# Safety_Loop.net
KiCad netlist of a schematic drawn in Altium Designer
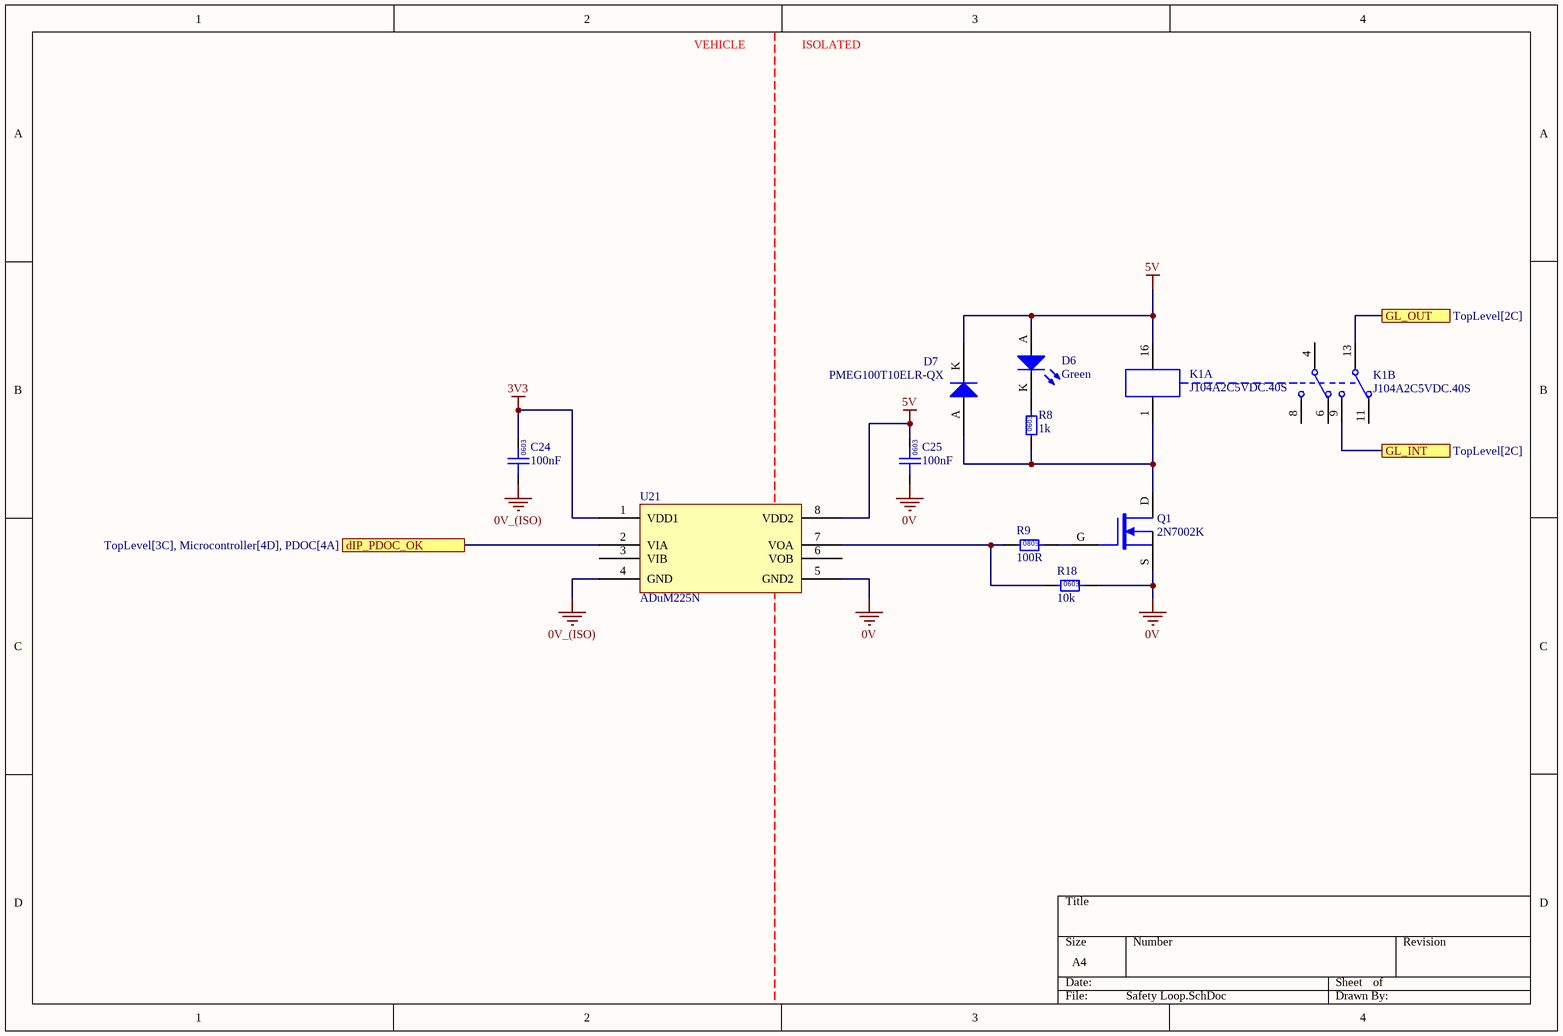
[diagram p0: Safety Loop.SchDoc]

(export (version "E")
  (design (tool "Eeschema 10.0.6"))
  (components
    (comp (ref "C24")
      (value "100nF")
      (footprint "0603")
      (fields
        (field (name "PART NUMBER") "GCM188L81H104KA57D")
        (field (name "MANUFACTURER") "muRata")
        (field (name "TOLERANCE") "±10%")
      )
      (libsource (lib "ts_standard_library") (part "Capacitor 0603"))
    )
    (comp (ref "C25")
      (value "100nF")
      (footprint "0603")
      (fields
        (field (name "PART NUMBER") "GCM188L81H104KA57D")
        (field (name "MANUFACTURER") "muRata")
        (field (name "TOLERANCE") "±10%")
      )
      (libsource (lib "ts_standard_library") (part "Capacitor 0603"))
    )
    (comp (ref "D6")
      (value "Green")
      (footprint "0805 LED")
      (description "Green LED Indication - Discrete 1.75V 0805 (2012 Metric)")
      (fields (field (name "PART NUMBER") "SML-210FTT86") (field (name "MANUFACTURER") "ROHM Semiconductor"))
      (libsource (lib "ts_standard_library") (part "LED"))
    )
    (comp (ref "D7")
      (value "PMEG100T10ELR-QX")
      (footprint "SODFL350X110-2N")
      (description "Diode 100 V 1A Surface Mount SOD-123W")
      (libsource (lib "Team Swinburne") (part "PMEG100T10ELR-QX"))
    )
    (comp (ref "K1")
      (value "J104A2C5VDC.40S")
      (footprint "J104A2C5VDC.40S-Footprint-1")
      (description "Relay Gen Purpose DPDT 3A 5V")
      (libsource (lib "") (part "J104A2C5VDC.40S_1"))
    )
    (comp (ref "Q1")
      (value "2N7002K")
      (footprint "2N7002K-Footprint-1")
      (description "60V 380mA, NFET MOSTFET (Small Signal)")
      (libsource (lib "Team Swinburne") (part "2N7002K"))
    )
    (comp (ref "R8")
      (value "1k")
      (footprint "0603")
      (fields
        (field (name "PART NUMBER") "RC0603FR-071KL")
        (field (name "MANUFACTURER") "YAGEO")
        (field (name "TOLERANCE") "0.01")
      )
      (libsource (lib "ts_standard_library") (part "Resistor 0603"))
    )
    (comp (ref "R9")
      (value "100R")
      (footprint "0805")
      (fields
        (field (name "PART NUMBER") "RC0805FR07100RL")
        (field (name "MANUFACTURER") "YAGEO")
        (field (name "TOLERANCE") "0.01")
      )
      (libsource (lib "ts_standard_library") (part "Resistor 0805"))
    )
    (comp (ref "R18")
      (value "10k")
      (footprint "0603")
      (fields
        (field (name "PART NUMBER") "RC0603FR-0710KL")
        (field (name "MANUFACTURER") "YAGEO")
        (field (name "TOLERANCE") "0.01")
      )
      (libsource (lib "ts_standard_library") (part "Resistor 0603"))
    )
    (comp (ref "U21")
      (value "ADuM225N")
      (footprint "AD-SOIC-8W")
      (description "DIGITAL ISOLATOR, DUAL CHANNEL")
      (fields (field (name "MANUFACTURER") "Analogue Devices"))
      (libsource (lib "ts_standard_library") (part "ADuM225N"))
    )
  )
  (nets
    (net (code "1") (name "/GL_INT") (class "Default")
      (node (ref "K1") (pin "9") (pinfunction "9_9") (pintype "passive"))
    )
    (net (code "2") (name "/GL_OUT") (class "Default")
      (node (ref "K1") (pin "13") (pinfunction "13_13") (pintype "passive"))
    )
    (net (code "3") (name "/dIP_PDOC_OK") (class "Default")
      (node (ref "U21") (pin "2") (pinfunction "VIA_2") (pintype "passive"))
    )
    (net (code "4") (name "0V") (class "Default")
      (node (ref "C25") (pin "1") (pinfunction "1_1") (pintype "passive"))
      (node (ref "Q1") (pin "S") (pinfunction "S_S") (pintype "passive"))
      (node (ref "R18") (pin "2") (pinfunction "2_2") (pintype "passive"))
      (node (ref "U21") (pin "5") (pinfunction "GND2_5") (pintype "passive"))
    )
    (net (code "5") (name "0V_(ISO)") (class "Default")
      (node (ref "C24") (pin "1") (pinfunction "1_1") (pintype "passive"))
      (node (ref "U21") (pin "4") (pinfunction "GND_4") (pintype "passive"))
    )
    (net (code "6") (name "3V3") (class "Default")
      (node (ref "C24") (pin "2") (pinfunction "2_2") (pintype "passive"))
      (node (ref "U21") (pin "1") (pinfunction "VDD1_1") (pintype "passive"))
    )
    (net (code "7") (name "5V") (class "Default")
      (node (ref "C25") (pin "2") (pinfunction "2_2") (pintype "passive"))
      (node (ref "D6") (pin "A") (pinfunction "A_A") (pintype "passive"))
      (node (ref "D7") (pin "K") (pintype "passive"))
      (node (ref "K1") (pin "16") (pinfunction "16_16") (pintype "passive"))
      (node (ref "U21") (pin "8") (pinfunction "VDD2_8") (pintype "passive"))
    )
    (net (code "8") (name "Net-(D6-PadK)") (class "Default")
      (node (ref "D6") (pin "K") (pinfunction "K_K") (pintype "passive"))
      (node (ref "R8") (pin "2") (pinfunction "2_2") (pintype "passive"))
    )
    (net (code "9") (name "Net-(D7-PadA)") (class "Default")
      (node (ref "D7") (pin "A") (pintype "passive"))
      (node (ref "K1") (pin "1") (pinfunction "1_1") (pintype "passive"))
      (node (ref "Q1") (pin "D") (pinfunction "D_D") (pintype "passive"))
      (node (ref "R8") (pin "1") (pinfunction "1_1") (pintype "passive"))
    )
    (net (code "10") (name "Net-(Q1-PadG)") (class "Default")
      (node (ref "Q1") (pin "G") (pinfunction "G_G") (pintype "passive"))
      (node (ref "R9") (pin "2") (pinfunction "2_2") (pintype "passive"))
    )
    (net (code "11") (name "Net-(U21-VOA)") (class "Default")
      (node (ref "R18") (pin "1") (pinfunction "1_1") (pintype "passive"))
      (node (ref "R9") (pin "1") (pinfunction "1_1") (pintype "passive"))
      (node (ref "U21") (pin "7") (pinfunction "VOA_7") (pintype "passive"))
    )
    (net (code "12") (name "unconnected-(K1-Pad4)") (class "Default")
      (node (ref "K1") (pin "4") (pinfunction "4_4") (pintype "passive"))
    )
    (net (code "13") (name "unconnected-(K1-Pad6)") (class "Default")
      (node (ref "K1") (pin "6") (pinfunction "6_6") (pintype "passive"))
    )
    (net (code "14") (name "unconnected-(K1-Pad8)") (class "Default")
      (node (ref "K1") (pin "8") (pinfunction "8_8") (pintype "passive"))
    )
    (net (code "15") (name "unconnected-(K1-Pad11)") (class "Default")
      (node (ref "K1") (pin "11") (pinfunction "11_11") (pintype "passive"))
    )
    (net (code "16") (name "unconnected-(U21-VIB-Pad3)") (class "Default")
      (node (ref "U21") (pin "3") (pinfunction "VIB_3") (pintype "passive"))
    )
    (net (code "17") (name "unconnected-(U21-VOB-Pad6)") (class "Default")
      (node (ref "U21") (pin "6") (pinfunction "VOB_6") (pintype "passive"))
    )
  )
)
